# LoraModule.net
KiCad netlist of a schematic drawn in Altium Designer
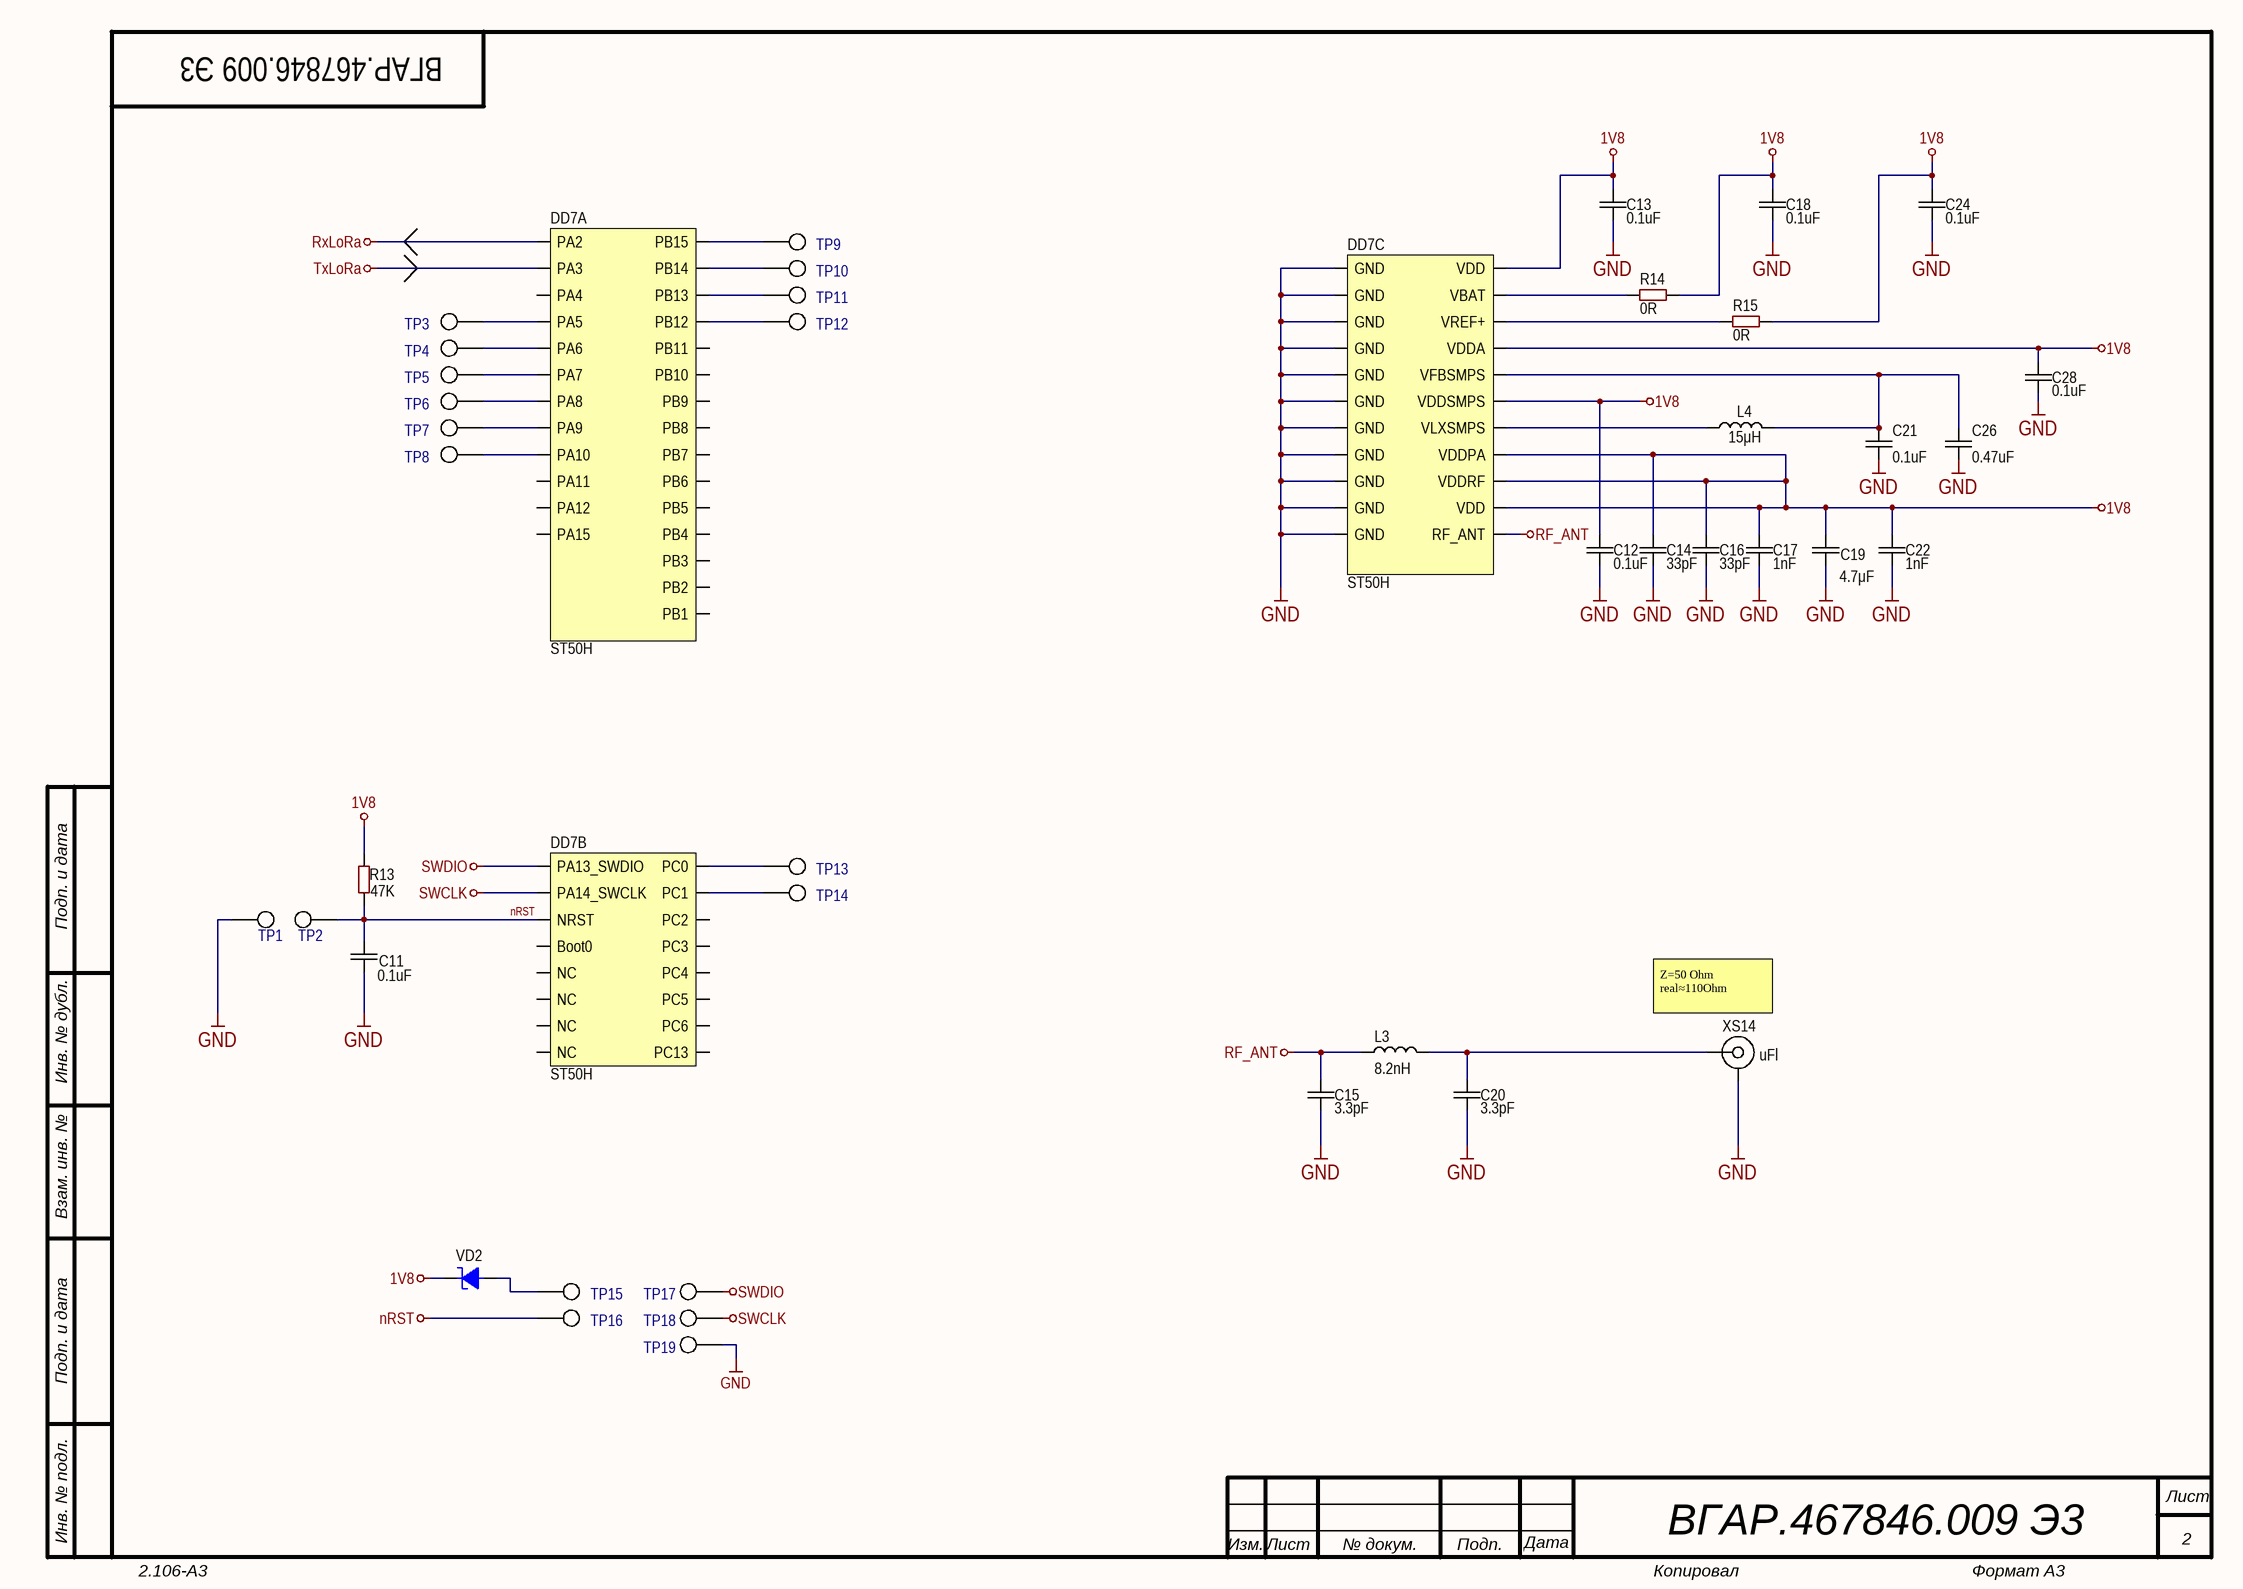
[diagram p0: LoraModule.SchDoc]

(export (version "E")
  (design (tool "Eeschema 10.0.6"))
  (components
    (comp (ref "C11")
      (value "0.1uF")
      (footprint "CAP: 0402")
      (fields
        (field (name "MANUFACTURER") "Yageo")
        (field (name "PARTNUMBER") "CC0402KRX7R7BB104")
        (field (name "VALUEMANUFACTURERPARTNUMBER") "Ceramic capacitor, 0.1uF, X7R, ±10%, 16V, 0402, -55...+125°C")
      )
      (libsource (lib "capacitor") (part "Ceramic_0402"))
    )
    (comp (ref "C12")
      (value "0.1uF")
      (footprint "CAP: 0402")
      (fields
        (field (name "MANUFACTURER") "Yageo")
        (field (name "PARTNUMBER") "CC0402KRX7R7BB104")
        (field (name "VALUEMANUFACTURERPARTNUMBER") "Ceramic capacitor, 0.1uF, X7R, ±10%, 16V, 0402, -55...+125°C")
      )
      (libsource (lib "capacitor") (part "Ceramic_0402"))
    )
    (comp (ref "C13")
      (value "0.1uF")
      (footprint "CAP: 0402")
      (fields
        (field (name "MANUFACTURER") "Yageo")
        (field (name "PARTNUMBER") "CC0402KRX7R7BB104")
        (field (name "VALUEMANUFACTURERPARTNUMBER") "Ceramic capacitor, 0.1uF, X7R, ±10%, 16V, 0402, -55...+125°C")
      )
      (libsource (lib "capacitor") (part "Ceramic_0402"))
    )
    (comp (ref "C14")
      (value "33pF")
      (footprint "CAP: 0402")
      (fields
        (field (name "MANUFACTURER") "Yageo")
        (field (name "PARTNUMBER") "CC0402KRX7R7BB104")
        (field (name "VALUEMANUFACTURERPARTNUMBER") "Ceramic capacitor, 33pF, X7R, ±10%, 16V, 0402, -55...+125°C")
      )
      (libsource (lib "capacitor") (part "Ceramic_0402"))
    )
    (comp (ref "C15")
      (value "3.3pF")
      (footprint "CAP: 0402")
      (fields
        (field (name "MANUFACTURER") "Yageo")
        (field (name "PARTNUMBER") "CC0402KRX7R7BB104")
        (field (name "VALUEMANUFACTURERPARTNUMBER") "Ceramic capacitor, 3.3pF, X7R, ±10%, 16V, 0402, -55...+125°C")
      )
      (libsource (lib "capacitor") (part "Ceramic_0402"))
    )
    (comp (ref "C16")
      (value "33pF")
      (footprint "CAP: 0402")
      (fields
        (field (name "MANUFACTURER") "Yageo")
        (field (name "PARTNUMBER") "CC0402KRX7R7BB104")
        (field (name "VALUEMANUFACTURERPARTNUMBER") "Ceramic capacitor, 33pF, X7R, ±10%, 16V, 0402, -55...+125°C")
      )
      (libsource (lib "capacitor") (part "Ceramic_0402"))
    )
    (comp (ref "C17")
      (value "1nF")
      (footprint "CAP: 0402")
      (fields
        (field (name "MANUFACTURER") "Yageo")
        (field (name "PARTNUMBER") "CC0402KRX7R7BB104")
        (field (name "VALUEMANUFACTURERPARTNUMBER") "Ceramic capacitor, 1nF, X7R, ±10%, 16V, 0402, -55...+125°C")
      )
      (libsource (lib "capacitor") (part "Ceramic_0402"))
    )
    (comp (ref "C18")
      (value "0.1uF")
      (footprint "CAP: 0402")
      (fields
        (field (name "MANUFACTURER") "Yageo")
        (field (name "PARTNUMBER") "CC0402KRX7R7BB104")
        (field (name "VALUEMANUFACTURERPARTNUMBER") "Ceramic capacitor, 0.1uF, X7R, ±10%, 16V, 0402, -55...+125°C")
      )
      (libsource (lib "capacitor") (part "Ceramic_0402"))
    )
    (comp (ref "C19")
      (value "4.7μF")
      (footprint "CAP: 0603")
      (fields
        (field (name "MANUFACTURER") "Yageo")
        (field (name "PARTNUMBER") "CC0603KRX7R7BB104")
        (field (name "VALUEMANUFACTURERPARTNUMBER") "Ceramic capacitor, 4.7μF, X7R, ±10%, 16V, 0603, -55...+125°C")
      )
      (libsource (lib "capacitor") (part "Ceramic_0603"))
    )
    (comp (ref "C20")
      (value "3.3pF")
      (footprint "CAP: 0402")
      (fields
        (field (name "MANUFACTURER") "Yageo")
        (field (name "PARTNUMBER") "CC0402KRX7R7BB104")
        (field (name "VALUEMANUFACTURERPARTNUMBER") "Ceramic capacitor, 3.3pF, X7R, ±10%, 16V, 0402, -55...+125°C")
      )
      (libsource (lib "capacitor") (part "Ceramic_0402"))
    )
    (comp (ref "C21")
      (value "0.1uF")
      (footprint "CAP: 0402")
      (fields
        (field (name "MANUFACTURER") "Yageo")
        (field (name "PARTNUMBER") "CC0402KRX7R7BB104")
        (field (name "VALUEMANUFACTURERPARTNUMBER") "Ceramic capacitor, 0.1uF, X7R, ±10%, 16V, 0402, -55...+125°C")
      )
      (libsource (lib "capacitor") (part "Ceramic_0402"))
    )
    (comp (ref "C22")
      (value "1nF")
      (footprint "CAP: 0402")
      (fields
        (field (name "MANUFACTURER") "Yageo")
        (field (name "PARTNUMBER") "CC0402KRX7R7BB104")
        (field (name "VALUEMANUFACTURERPARTNUMBER") "Ceramic capacitor, 1nF, X7R, ±10%, 16V, 0402, -55...+125°C")
      )
      (libsource (lib "capacitor") (part "Ceramic_0402"))
    )
    (comp (ref "C24")
      (value "0.1uF")
      (footprint "CAP: 0402")
      (fields
        (field (name "MANUFACTURER") "Yageo")
        (field (name "PARTNUMBER") "CC0402KRX7R7BB104")
        (field (name "VALUEMANUFACTURERPARTNUMBER") "Ceramic capacitor, 0.1uF, X7R, ±10%, 16V, 0402, -55...+125°C")
      )
      (libsource (lib "capacitor") (part "Ceramic_0402"))
    )
    (comp (ref "C26")
      (value "0.47uF")
      (footprint "CAP: 0402")
      (fields
        (field (name "MANUFACTURER") "Yageo")
        (field (name "PARTNUMBER") "CC0402KRX7R7BB104")
        (field (name "VALUEMANUFACTURERPARTNUMBER") "Ceramic capacitor, 0.47uF, X7R, ±10%, 16V, 0402, -55...+125°C")
      )
      (libsource (lib "capacitor") (part "Ceramic_0402"))
    )
    (comp (ref "C28")
      (value "0.1uF")
      (footprint "CAP: 0402")
      (fields
        (field (name "MANUFACTURER") "Yageo")
        (field (name "PARTNUMBER") "CC0402KRX7R7BB104")
        (field (name "VALUEMANUFACTURERPARTNUMBER") "Ceramic capacitor, 0.1uF, X7R, ±10%, 16V, 0402, -55...+125°C")
      )
      (libsource (lib "capacitor") (part "Ceramic_0402"))
    )
    (comp (ref "DD7")
      (value "ST50H")
      (footprint "ST50H")
      (description "LoRa module")
      (libsource (lib "") (part "ST50H_1"))
    )
    (comp (ref "L3")
      (value "8.2nH")
      (footprint "IND: 0402")
      (fields
        (field (name "MANUFACTURER") "Murata Electronics")
        (field (name "PARTNUMBER") "LQG15HSR10J02D")
        (field (name "VALUEMANUFACTURERPARTNUMBER") "Fixed inductor, 8.2nH, ±5%, 0402, 200mA, -55...+125°C")
      )
      (libsource (lib "inductor") (part "Inductor_0402"))
    )
    (comp (ref "L4")
      (value "15μH")
      (footprint "IND: 0805")
      (fields
        (field (name "MANUFACTURER") "Murata Electronics")
        (field (name "PARTNUMBER") "LQM21FN100M70L")
        (field (name "VALUEMANUFACTURERPARTNUMBER") "Fixed inductor, 15μH, ±20%, 0805, 100mA, -55...+125°C")
      )
      (libsource (lib "inductor") (part "Inductor_0805"))
    )
    (comp (ref "R13")
      (value "47K")
      (footprint "RES: 0402")
      (fields
        (field (name "MANUFACTURER") "Yageo")
        (field (name "PARTNUMBER") "RC0402JR-07100RL")
        (field (name "VALUEMANUFACTURERPARTNUMBER") "Resistor film, 47K, ±5%, 0402, 0.063W, -55...+125°C")
      )
      (libsource (lib "") (part "Resistor_0402_1"))
    )
    (comp (ref "R14")
      (value "0R")
      (footprint "RES: 0402")
      (fields
        (field (name "MANUFACTURER") "Yageo")
        (field (name "PARTNUMBER") "RC0402JR-07100RL")
        (field (name "VALUEMANUFACTURERPARTNUMBER") "Resistor film, 0R, ±5%, 0402, 0.063W, -55...+125°C")
      )
      (libsource (lib "resistor") (part "Resistor_0402"))
    )
    (comp (ref "R15")
      (value "0R")
      (footprint "RES: 0402")
      (fields
        (field (name "MANUFACTURER") "Yageo")
        (field (name "PARTNUMBER") "RC0402JR-07100RL")
        (field (name "VALUEMANUFACTURERPARTNUMBER") "Resistor film, 0R, ±5%, 0402, 0.063W, -55...+125°C")
      )
      (libsource (lib "resistor") (part "Resistor_0402"))
    )
    (comp (ref "TP1")
      (value "Testpoint_HS1mm")
      (footprint "TestPoint(without 3D)")
      (libsource (lib "connector") (part "Testpoint_HS1mm"))
    )
    (comp (ref "TP2")
      (value "Testpoint_HS1mm")
      (footprint "TestPoint(without 3D)")
      (libsource (lib "connector") (part "Testpoint_HS1mm"))
    )
    (comp (ref "TP3")
      (value "Testpoint_HS1mm")
      (footprint "TestPoint(without hole)")
      (libsource (lib "connector") (part "Testpoint_HS1mm"))
    )
    (comp (ref "TP4")
      (value "Testpoint_HS1mm")
      (footprint "TestPoint(without hole)")
      (libsource (lib "connector") (part "Testpoint_HS1mm"))
    )
    (comp (ref "TP5")
      (value "Testpoint_HS1mm")
      (footprint "TestPoint(without hole)")
      (libsource (lib "connector") (part "Testpoint_HS1mm"))
    )
    (comp (ref "TP6")
      (value "Testpoint_HS1mm")
      (footprint "TestPoint(without hole)")
      (libsource (lib "connector") (part "Testpoint_HS1mm"))
    )
    (comp (ref "TP7")
      (value "Testpoint_HS1mm")
      (footprint "TestPoint(without hole)")
      (libsource (lib "connector") (part "Testpoint_HS1mm"))
    )
    (comp (ref "TP8")
      (value "Testpoint_HS1mm")
      (footprint "TestPoint(without hole)")
      (libsource (lib "connector") (part "Testpoint_HS1mm"))
    )
    (comp (ref "TP9")
      (value "Testpoint_HS1mm")
      (footprint "TestPoint(without hole)")
      (libsource (lib "connector") (part "Testpoint_HS1mm"))
    )
    (comp (ref "TP10")
      (value "Testpoint_HS1mm")
      (footprint "TestPoint(without hole)")
      (libsource (lib "connector") (part "Testpoint_HS1mm"))
    )
    (comp (ref "TP11")
      (value "Testpoint_HS1mm")
      (footprint "TestPoint(without hole)")
      (libsource (lib "connector") (part "Testpoint_HS1mm"))
    )
    (comp (ref "TP12")
      (value "Testpoint_HS1mm")
      (footprint "TestPoint(without hole)")
      (libsource (lib "connector") (part "Testpoint_HS1mm"))
    )
    (comp (ref "TP13")
      (value "Testpoint_HS1mm")
      (footprint "TestPoint(without hole)")
      (libsource (lib "connector") (part "Testpoint_HS1mm"))
    )
    (comp (ref "TP14")
      (value "Testpoint_HS1mm")
      (footprint "TestPoint(without hole)")
      (libsource (lib "connector") (part "Testpoint_HS1mm"))
    )
    (comp (ref "TP15")
      (value "Testpoint_HS1mm")
      (footprint "TestPoint(without hole)")
      (libsource (lib "connector") (part "Testpoint_HS1mm"))
    )
    (comp (ref "TP16")
      (value "Testpoint_HS1mm")
      (footprint "TestPoint(without hole)")
      (libsource (lib "connector") (part "Testpoint_HS1mm"))
    )
    (comp (ref "TP17")
      (value "Testpoint_HS1mm")
      (footprint "TestPoint(without hole)")
      (libsource (lib "connector") (part "Testpoint_HS1mm"))
    )
    (comp (ref "TP18")
      (value "Testpoint_HS1mm")
      (footprint "TestPoint(without hole)")
      (libsource (lib "connector") (part "Testpoint_HS1mm"))
    )
    (comp (ref "TP19")
      (value "Testpoint_HS1mm")
      (footprint "TestPoint(without hole)")
      (libsource (lib "connector") (part "Testpoint_HS1mm"))
    )
    (comp (ref "VD2")
      (value "~")
      (footprint "DIODE: SOD523")
      (fields
        (field (name "MANUFACTURER") "Diodes Incorporated")
        (field (name "VALUEMANUFACTURERPARTNUMBER") "Schottky diode, 80V, 500mA, 1V, 15pF, SOD-123, -55...+150°C")
        (field (name "VOLTAGE") "80V")
      )
      (libsource (lib "diode") (part "Schottky_single"))
    )
    (comp (ref "XS14")
      (value "~")
      (footprint "CON: u.Fl")
      (fields
        (field (name "MANUFACTURER") "Hirose Electric")
        (field (name "VALUEMANUFACTURERPARTNUMBER") "Connector u.FL, 50 Ohm, 6GHz")
        (field (name "PARTNUMBER") "U.FL-R-SMT(01)")
        (field (name "COMMENTTEXT") "uFl")
      )
      (libsource (lib "connector") (part "Connector_uFL"))
    )
  )
  (nets
    (net (code "1") (name "1V8") (class "Default")
      (node (ref "C12") (pin "2") (pinfunction "2_2") (pintype "passive"))
      (node (ref "C13") (pin "2") (pinfunction "2_2") (pintype "passive"))
      (node (ref "C14") (pin "2") (pinfunction "2_2") (pintype "passive"))
      (node (ref "C16") (pin "2") (pinfunction "2_2") (pintype "passive"))
      (node (ref "C17") (pin "2") (pinfunction "2_2") (pintype "passive"))
      (node (ref "C18") (pin "2") (pinfunction "2_2") (pintype "passive"))
      (node (ref "C19") (pin "2") (pinfunction "2_2") (pintype "passive"))
      (node (ref "C22") (pin "2") (pinfunction "2_2") (pintype "passive"))
      (node (ref "C24") (pin "2") (pinfunction "2_2") (pintype "passive"))
      (node (ref "C28") (pin "2") (pinfunction "2_2") (pintype "passive"))
      (node (ref "DD7") (pin "11") (pinfunction "VDDSMPS_11") (pintype "passive"))
      (node (ref "DD7") (pin "3") (pinfunction "VDD_3") (pintype "passive"))
      (node (ref "DD7") (pin "53") (pinfunction "VDDPA_53") (pintype "passive"))
      (node (ref "DD7") (pin "54") (pinfunction "VDDRF_54") (pintype "passive"))
      (node (ref "DD7") (pin "55") (pinfunction "VDD_55") (pintype "passive"))
      (node (ref "DD7") (pin "7") (pinfunction "VDDA_7") (pintype "passive"))
      (node (ref "R13") (pin "2") (pinfunction "2_2") (pintype "passive"))
      (node (ref "R14") (pin "1") (pinfunction "1_1") (pintype "passive"))
      (node (ref "R15") (pin "1") (pinfunction "1_1") (pintype "passive"))
      (node (ref "VD2") (pin "2") (pinfunction "2_2") (pintype "passive"))
    )
    (net (code "2") (name "GND") (class "Default")
      (node (ref "C11") (pin "1") (pinfunction "1_1") (pintype "passive"))
      (node (ref "C12") (pin "1") (pinfunction "1_1") (pintype "passive"))
      (node (ref "C13") (pin "1") (pinfunction "1_1") (pintype "passive"))
      (node (ref "C14") (pin "1") (pinfunction "1_1") (pintype "passive"))
      (node (ref "C15") (pin "1") (pinfunction "1_1") (pintype "passive"))
      (node (ref "C16") (pin "1") (pinfunction "1_1") (pintype "passive"))
      (node (ref "C17") (pin "1") (pinfunction "1_1") (pintype "passive"))
      (node (ref "C18") (pin "1") (pinfunction "1_1") (pintype "passive"))
      (node (ref "C19") (pin "1") (pinfunction "1_1") (pintype "passive"))
      (node (ref "C20") (pin "1") (pinfunction "1_1") (pintype "passive"))
      (node (ref "C21") (pin "1") (pinfunction "1_1") (pintype "passive"))
      (node (ref "C22") (pin "1") (pinfunction "1_1") (pintype "passive"))
      (node (ref "C24") (pin "1") (pinfunction "1_1") (pintype "passive"))
      (node (ref "C26") (pin "2") (pinfunction "2_2") (pintype "passive"))
      (node (ref "C28") (pin "1") (pinfunction "1_1") (pintype "passive"))
      (node (ref "DD7") (pin "12") (pinfunction "GND_12") (pintype "passive"))
      (node (ref "DD7") (pin "28") (pinfunction "GND_28") (pintype "passive"))
      (node (ref "DD7") (pin "35") (pinfunction "GND_35") (pintype "passive"))
      (node (ref "DD7") (pin "36") (pinfunction "GND_36") (pintype "passive"))
      (node (ref "DD7") (pin "38") (pinfunction "GND_38") (pintype "passive"))
      (node (ref "DD7") (pin "39") (pinfunction "GND_39") (pintype "passive"))
      (node (ref "DD7") (pin "46") (pinfunction "GND_46") (pintype "passive"))
      (node (ref "DD7") (pin "47") (pinfunction "GND_47") (pintype "passive"))
      (node (ref "DD7") (pin "52") (pinfunction "GND_52") (pintype "passive"))
      (node (ref "DD7") (pin "56") (pinfunction "GND_56") (pintype "passive"))
      (node (ref "DD7") (pin "65") (pinfunction "GND_65") (pintype "passive"))
      (node (ref "TP1") (pin "1") (pinfunction "1_1") (pintype "passive"))
      (node (ref "TP19") (pin "1") (pinfunction "1_1") (pintype "passive"))
      (node (ref "XS14") (pin "2") (pinfunction "2_2") (pintype "passive"))
    )
    (net (code "3") (name "Net-(C20-Pad2)") (class "Default")
      (node (ref "C20") (pin "2") (pinfunction "2_2") (pintype "passive"))
      (node (ref "L3") (pin "2") (pinfunction "2_2") (pintype "passive"))
      (node (ref "XS14") (pin "1") (pinfunction "1_1") (pintype "passive"))
    )
    (net (code "4") (name "Net-(DD7A-PA5)") (class "Default")
      (node (ref "DD7") (pin "32") (pinfunction "PA5_32") (pintype "passive"))
      (node (ref "TP3") (pin "1") (pinfunction "1_1") (pintype "passive"))
    )
    (net (code "5") (name "Net-(DD7A-PA6)") (class "Default")
      (node (ref "DD7") (pin "33") (pinfunction "PA6_33") (pintype "passive"))
      (node (ref "TP4") (pin "1") (pinfunction "1_1") (pintype "passive"))
    )
    (net (code "6") (name "Net-(DD7A-PA7)") (class "Default")
      (node (ref "DD7") (pin "34") (pinfunction "PA7_34") (pintype "passive"))
      (node (ref "TP5") (pin "1") (pinfunction "1_1") (pintype "passive"))
    )
    (net (code "7") (name "Net-(DD7A-PA8)") (class "Default")
      (node (ref "DD7") (pin "51") (pinfunction "PA8_51") (pintype "passive"))
      (node (ref "TP6") (pin "1") (pinfunction "1_1") (pintype "passive"))
    )
    (net (code "8") (name "Net-(DD7A-PA9)") (class "Default")
      (node (ref "DD7") (pin "50") (pinfunction "PA9_50") (pintype "passive"))
      (node (ref "TP7") (pin "1") (pinfunction "1_1") (pintype "passive"))
    )
    (net (code "9") (name "Net-(DD7A-PA10)") (class "Default")
      (node (ref "DD7") (pin "62") (pinfunction "PA10_62") (pintype "passive"))
      (node (ref "TP8") (pin "1") (pinfunction "1_1") (pintype "passive"))
    )
    (net (code "10") (name "Net-(DD7A-PB12)") (class "Default")
      (node (ref "DD7") (pin "59") (pinfunction "PB12_59") (pintype "passive"))
      (node (ref "TP12") (pin "1") (pinfunction "1_1") (pintype "passive"))
    )
    (net (code "11") (name "Net-(DD7A-PB13)") (class "Default")
      (node (ref "DD7") (pin "60") (pinfunction "PB13_60") (pintype "passive"))
      (node (ref "TP11") (pin "1") (pinfunction "1_1") (pintype "passive"))
    )
    (net (code "12") (name "Net-(DD7A-PB14)") (class "Default")
      (node (ref "DD7") (pin "61") (pinfunction "PB14_61") (pintype "passive"))
      (node (ref "TP10") (pin "1") (pinfunction "1_1") (pintype "passive"))
    )
    (net (code "13") (name "Net-(DD7A-PB15)") (class "Default")
      (node (ref "DD7") (pin "9") (pinfunction "PB15_9") (pintype "passive"))
      (node (ref "TP9") (pin "1") (pinfunction "1_1") (pintype "passive"))
    )
    (net (code "14") (name "Net-(DD7B-PC0)") (class "Default")
      (node (ref "DD7") (pin "21") (pinfunction "PC0_21") (pintype "passive"))
      (node (ref "TP13") (pin "1") (pinfunction "1_1") (pintype "passive"))
    )
    (net (code "15") (name "Net-(DD7B-PC1)") (class "Default")
      (node (ref "DD7") (pin "22") (pinfunction "PC1_22") (pintype "passive"))
      (node (ref "TP14") (pin "1") (pinfunction "1_1") (pintype "passive"))
    )
    (net (code "16") (name "Net-(DD7C-VBAT)") (class "Default")
      (node (ref "DD7") (pin "4") (pinfunction "VBAT_4") (pintype "passive"))
      (node (ref "R14") (pin "2") (pinfunction "2_2") (pintype "passive"))
    )
    (net (code "17") (name "Net-(DD7C-VFBSMPS)") (class "Default")
      (node (ref "C21") (pin "2") (pinfunction "2_2") (pintype "passive"))
      (node (ref "C26") (pin "1") (pinfunction "1_1") (pintype "passive"))
      (node (ref "DD7") (pin "10") (pinfunction "VFBSMPS_10") (pintype "passive"))
      (node (ref "L4") (pin "2") (pinfunction "2_2") (pintype "passive"))
    )
    (net (code "18") (name "Net-(DD7C-VLXSMPS)") (class "Default")
      (node (ref "DD7") (pin "13") (pinfunction "VLXSMPS_13") (pintype "passive"))
      (node (ref "L4") (pin "1") (pinfunction "1_1") (pintype "passive"))
    )
    (net (code "19") (name "Net-(DD7C-VREF+)") (class "Default")
      (node (ref "DD7") (pin "6") (pinfunction "VREF+_6") (pintype "passive"))
      (node (ref "R15") (pin "2") (pinfunction "2_2") (pintype "passive"))
    )
    (net (code "20") (name "Net-(TP15-Pad1)") (class "Default")
      (node (ref "TP15") (pin "1") (pinfunction "1_1") (pintype "passive"))
      (node (ref "VD2") (pin "1") (pinfunction "1_1") (pintype "passive"))
    )
    (net (code "21") (name "RF_ANT") (class "Default")
      (node (ref "C15") (pin "2") (pinfunction "2_2") (pintype "passive"))
      (node (ref "DD7") (pin "37") (pinfunction "RF_ANT_37") (pintype "passive"))
      (node (ref "L3") (pin "1") (pinfunction "1_1") (pintype "passive"))
    )
    (net (code "22") (name "RxLoRa") (class "Default")
      (node (ref "DD7") (pin "29") (pinfunction "PA2_29") (pintype "passive"))
    )
    (net (code "23") (name "SWCLK") (class "Default")
      (node (ref "DD7") (pin "2") (pinfunction "PA14_SWCLK_2") (pintype "passive"))
      (node (ref "TP18") (pin "1") (pinfunction "1_1") (pintype "passive"))
    )
    (net (code "24") (name "SWDIO") (class "Default")
      (node (ref "DD7") (pin "1") (pinfunction "PA13_SWDIO_1") (pintype "passive"))
      (node (ref "TP17") (pin "1") (pinfunction "1_1") (pintype "passive"))
    )
    (net (code "25") (name "TxLoRa") (class "Default")
      (node (ref "DD7") (pin "30") (pinfunction "PA3_30") (pintype "passive"))
    )
    (net (code "26") (name "nRST") (class "Default")
      (node (ref "C11") (pin "2") (pinfunction "2_2") (pintype "passive"))
      (node (ref "DD7") (pin "44") (pinfunction "NRST_44") (pintype "passive"))
      (node (ref "R13") (pin "1") (pinfunction "1_1") (pintype "passive"))
      (node (ref "TP16") (pin "1") (pinfunction "1_1") (pintype "passive"))
      (node (ref "TP2") (pin "1") (pinfunction "1_1") (pintype "passive"))
    )
    (net (code "27") (name "unconnected-(DD7A-PA4-Pad31)") (class "Default")
      (node (ref "DD7") (pin "31") (pinfunction "PA4_31") (pintype "passive"))
    )
    (net (code "28") (name "unconnected-(DD7A-PA11-Pad63)") (class "Default")
      (node (ref "DD7") (pin "63") (pinfunction "PA11_63") (pintype "passive"))
    )
    (net (code "29") (name "unconnected-(DD7A-PA12-Pad64)") (class "Default")
      (node (ref "DD7") (pin "64") (pinfunction "PA12_64") (pintype "passive"))
    )
    (net (code "30") (name "unconnected-(DD7A-PA15-Pad8)") (class "Default")
      (node (ref "DD7") (pin "8") (pinfunction "PA15_8") (pintype "passive"))
    )
    (net (code "31") (name "unconnected-(DD7A-PB1-Pad57)") (class "Default")
      (node (ref "DD7") (pin "57") (pinfunction "PB1_57") (pintype "passive"))
    )
    (net (code "32") (name "unconnected-(DD7A-PB2-Pad58)") (class "Default")
      (node (ref "DD7") (pin "58") (pinfunction "PB2_58") (pintype "passive"))
    )
    (net (code "33") (name "unconnected-(DD7A-PB3-Pad14)") (class "Default")
      (node (ref "DD7") (pin "14") (pinfunction "PB3_14") (pintype "passive"))
    )
    (net (code "34") (name "unconnected-(DD7A-PB4-Pad15)") (class "Default")
      (node (ref "DD7") (pin "15") (pinfunction "PB4_15") (pintype "passive"))
    )
    (net (code "35") (name "unconnected-(DD7A-PB5-Pad16)") (class "Default")
      (node (ref "DD7") (pin "16") (pinfunction "PB5_16") (pintype "passive"))
    )
    (net (code "36") (name "unconnected-(DD7A-PB6-Pad17)") (class "Default")
      (node (ref "DD7") (pin "17") (pinfunction "PB6_17") (pintype "passive"))
    )
    (net (code "37") (name "unconnected-(DD7A-PB7-Pad18)") (class "Default")
      (node (ref "DD7") (pin "18") (pinfunction "PB7_18") (pintype "passive"))
    )
    (net (code "38") (name "unconnected-(DD7A-PB8-Pad19)") (class "Default")
      (node (ref "DD7") (pin "19") (pinfunction "PB8_19") (pintype "passive"))
    )
    (net (code "39") (name "unconnected-(DD7A-PB9-Pad20)") (class "Default")
      (node (ref "DD7") (pin "20") (pinfunction "PB9_20") (pintype "passive"))
    )
    (net (code "40") (name "unconnected-(DD7A-PB10-Pad49)") (class "Default")
      (node (ref "DD7") (pin "49") (pinfunction "PB10_49") (pintype "passive"))
    )
    (net (code "41") (name "unconnected-(DD7A-PB11-Pad48)") (class "Default")
      (node (ref "DD7") (pin "48") (pinfunction "PB11_48") (pintype "passive"))
    )
    (net (code "42") (name "unconnected-(DD7B-Boot0-Pad43)") (class "Default")
      (node (ref "DD7") (pin "43") (pinfunction "Boot0_43") (pintype "passive"))
    )
    (net (code "43") (name "unconnected-(DD7B-NC-Pad40)") (class "Default")
      (node (ref "DD7") (pin "40") (pinfunction "NC_40") (pintype "passive"))
    )
    (net (code "44") (name "unconnected-(DD7B-NC-Pad41)") (class "Default")
      (node (ref "DD7") (pin "41") (pinfunction "NC_41") (pintype "passive"))
    )
    (net (code "45") (name "unconnected-(DD7B-NC-Pad42)") (class "Default")
      (node (ref "DD7") (pin "42") (pinfunction "NC_42") (pintype "passive"))
    )
    (net (code "46") (name "unconnected-(DD7B-NC-Pad45)") (class "Default")
      (node (ref "DD7") (pin "45") (pinfunction "NC_45") (pintype "passive"))
    )
    (net (code "47") (name "unconnected-(DD7B-PC2-Pad23)") (class "Default")
      (node (ref "DD7") (pin "23") (pinfunction "PC2_23") (pintype "passive"))
    )
    (net (code "48") (name "unconnected-(DD7B-PC3-Pad24)") (class "Default")
      (node (ref "DD7") (pin "24") (pinfunction "PC3_24") (pintype "passive"))
    )
    (net (code "49") (name "unconnected-(DD7B-PC4-Pad25)") (class "Default")
      (node (ref "DD7") (pin "25") (pinfunction "PC4_25") (pintype "passive"))
    )
    (net (code "50") (name "unconnected-(DD7B-PC5-Pad26)") (class "Default")
      (node (ref "DD7") (pin "26") (pinfunction "PC5_26") (pintype "passive"))
    )
    (net (code "51") (name "unconnected-(DD7B-PC6-Pad27)") (class "Default")
      (node (ref "DD7") (pin "27") (pinfunction "PC6_27") (pintype "passive"))
    )
    (net (code "52") (name "unconnected-(DD7B-PC13-Pad5)") (class "Default")
      (node (ref "DD7") (pin "5") (pinfunction "PC13_5") (pintype "passive"))
    )
  )
)
